# New_Multirotor_CPU_imu.net
KiCad netlist of a schematic drawn in EAGLE
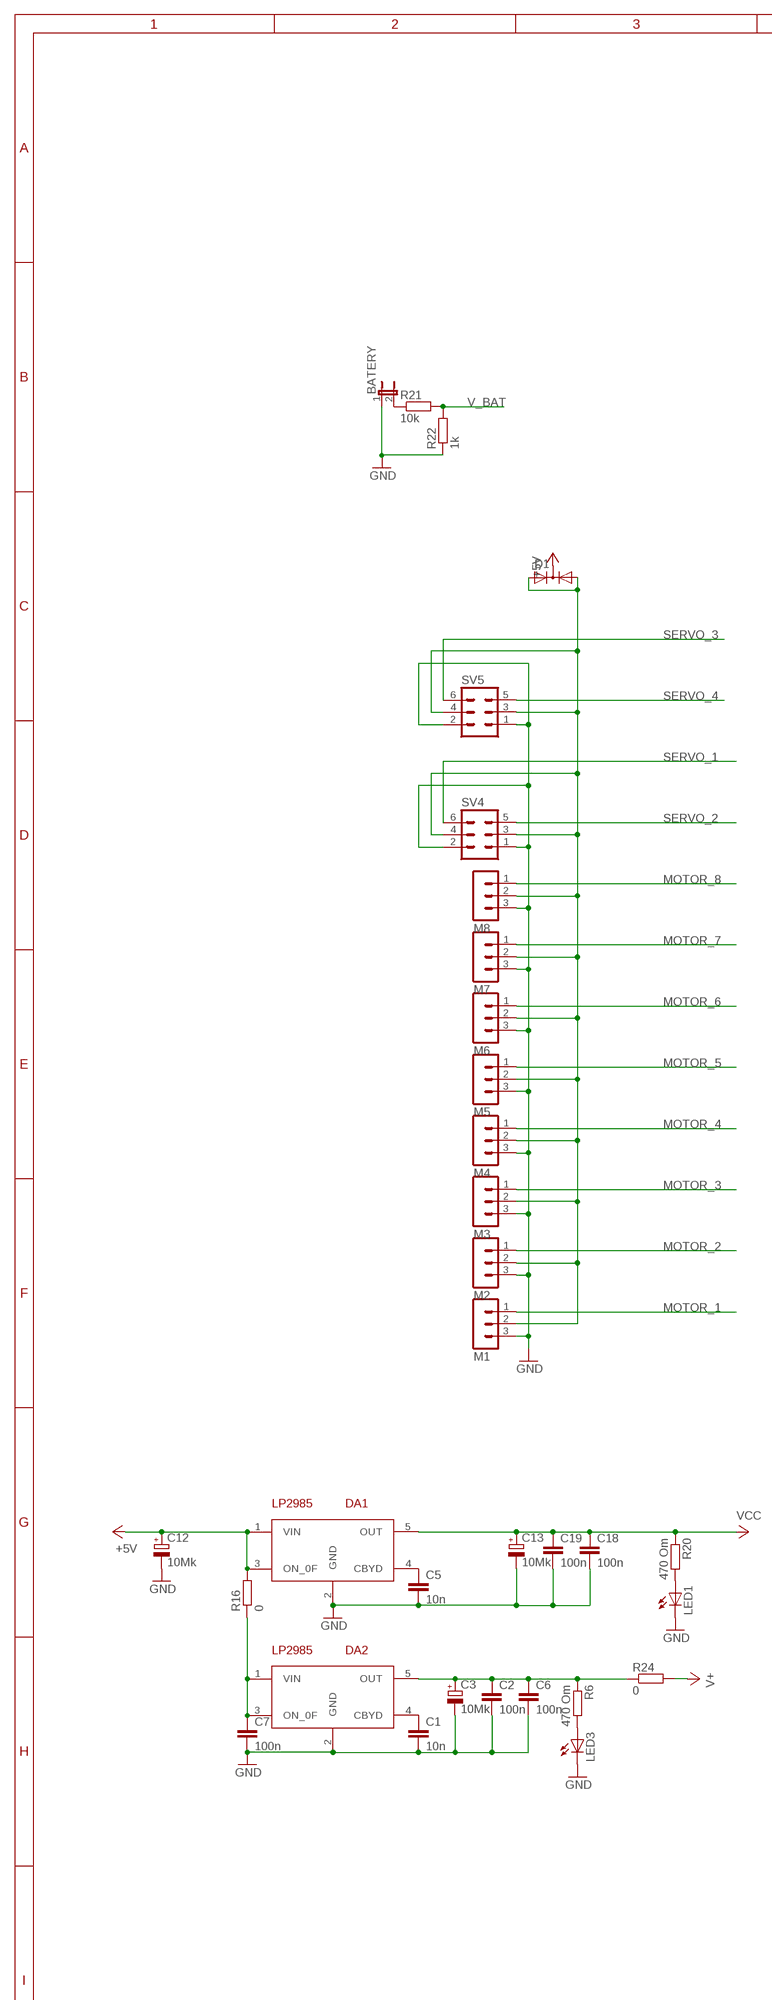
[diagram p0: schematic, sheet 1, part 1 of 2]
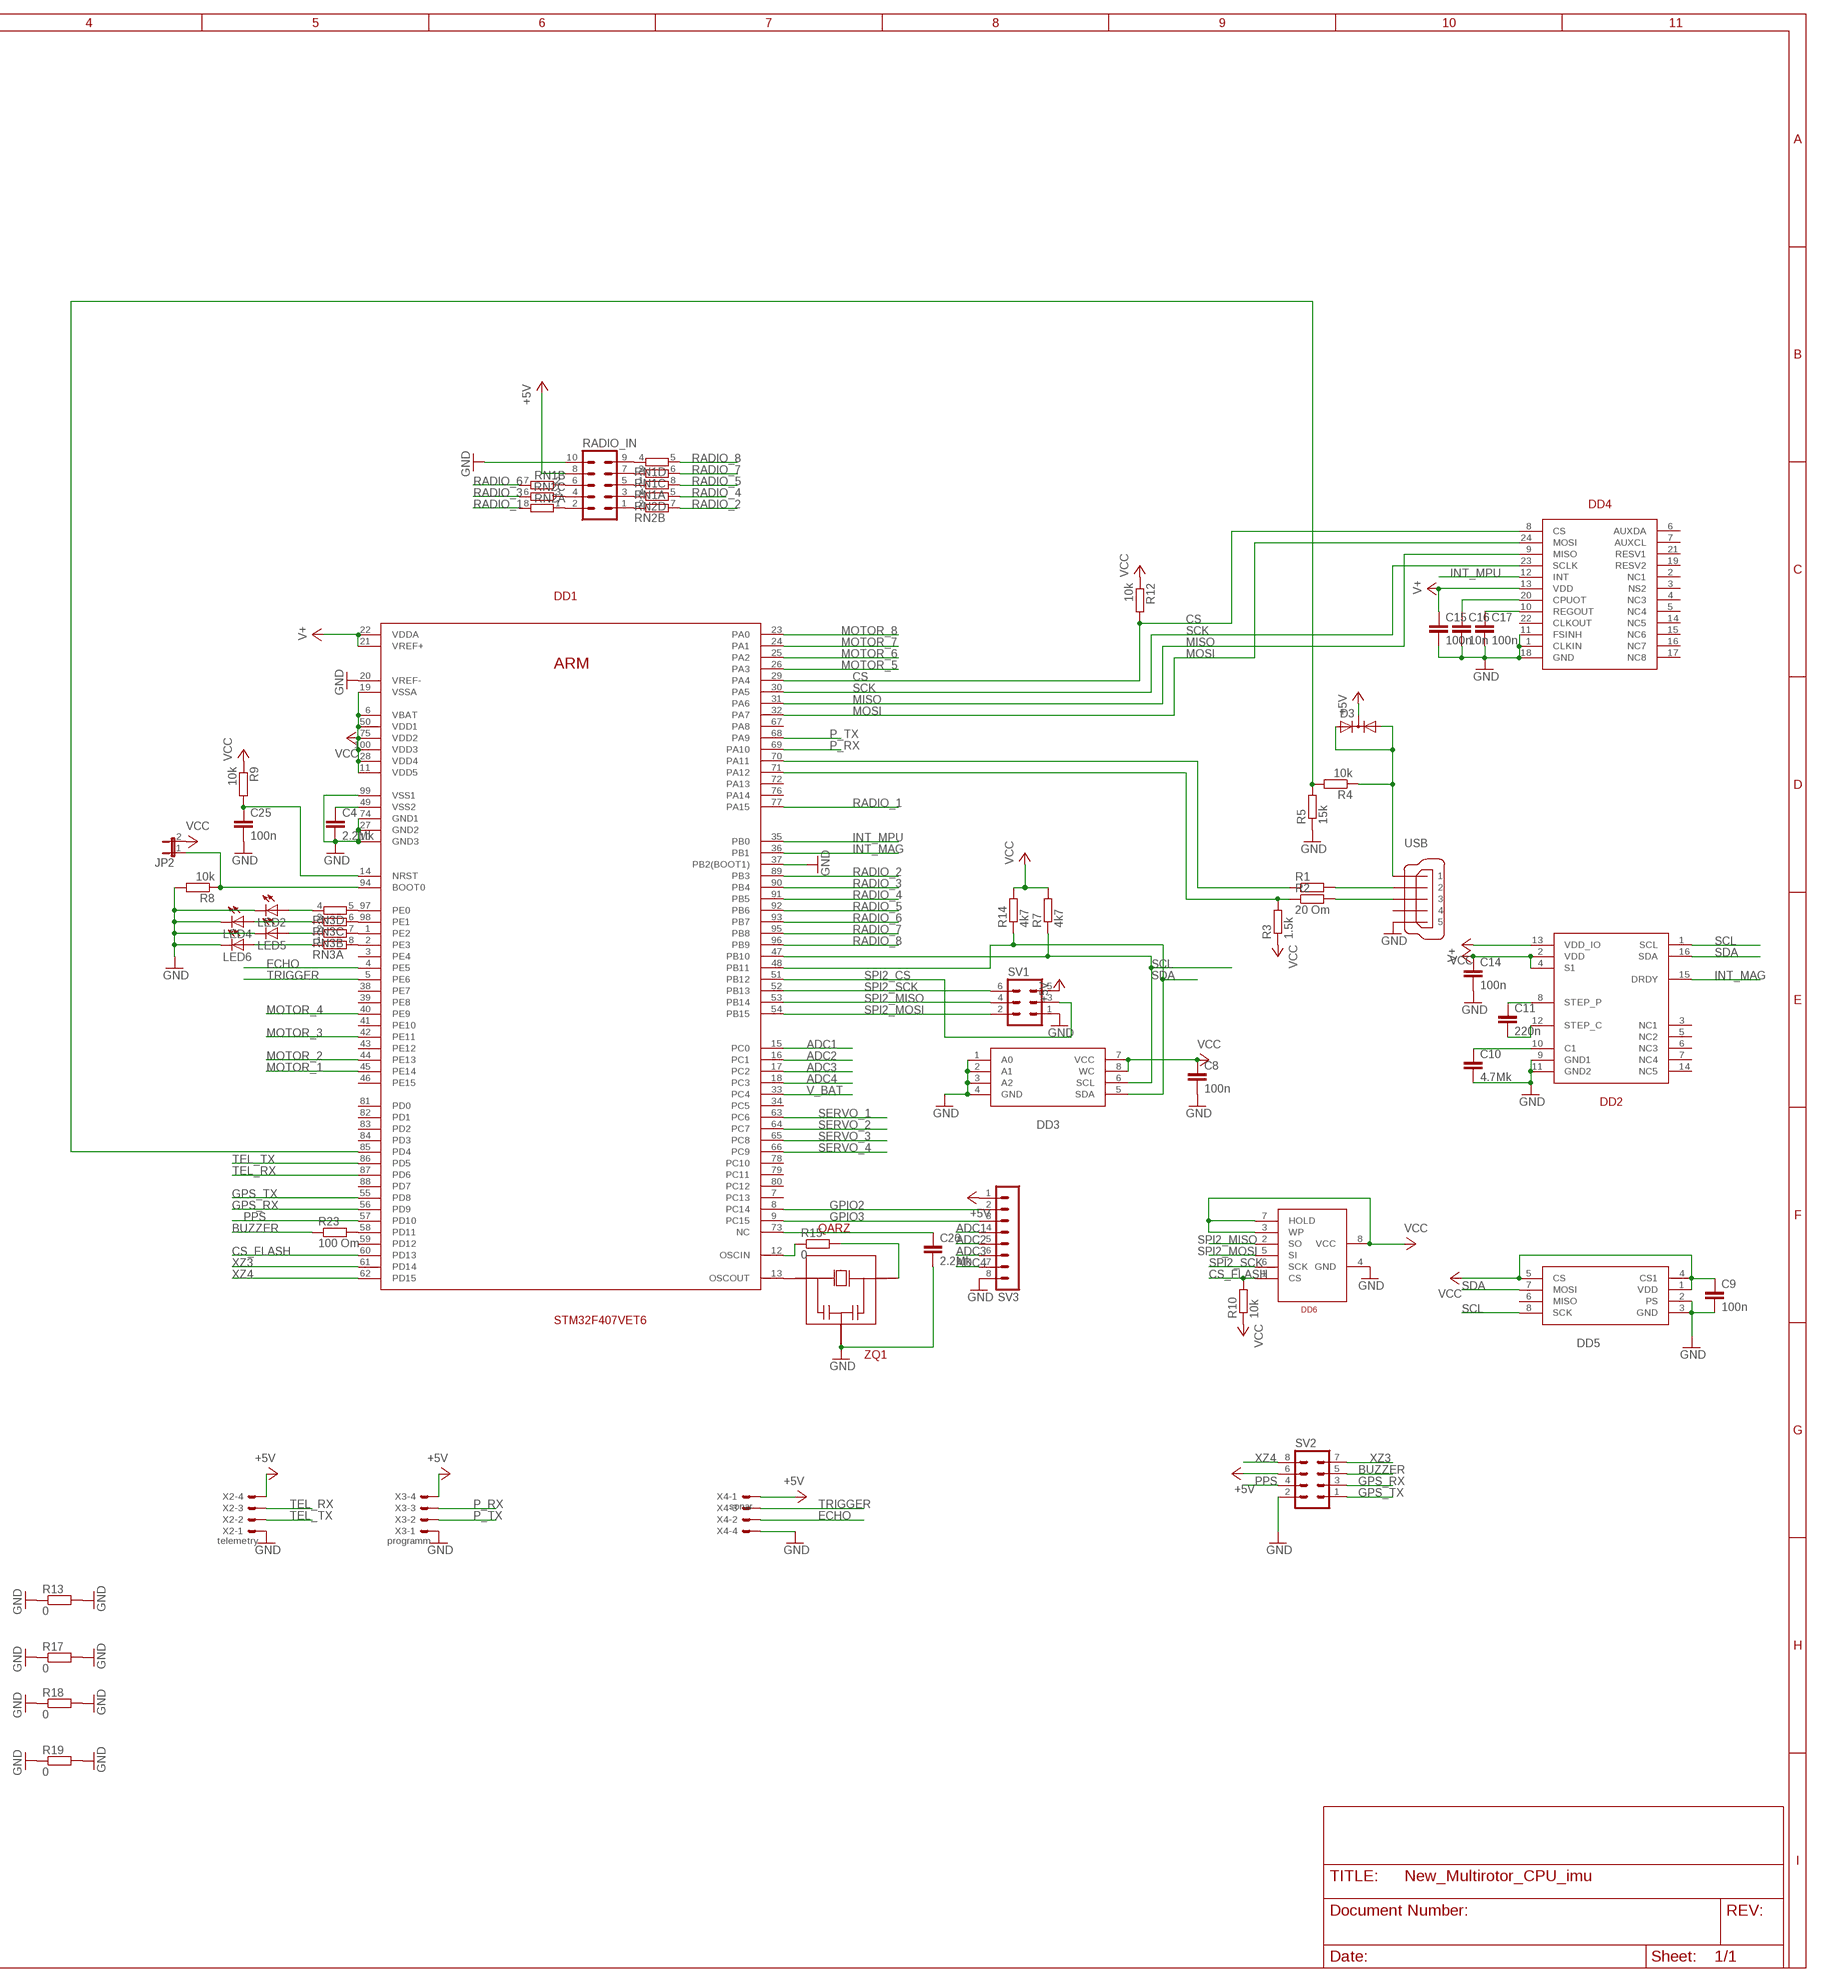
[diagram p1: schematic, sheet 1, part 2 of 2]

(export (version "E")
  (design (tool "Eeschema 10.0.6"))
  (components
    (comp (ref "BATERY")
      (value "JP1E")
      (footprint "eagle-import:JP1")
      (libsource (lib "eagle-import") (part "JP1E"))
    )
    (comp (ref "C1")
      (value "10n")
      (footprint "eagle-import:C0603K")
      (libsource (lib "eagle-import") (part "C-EUC0603K"))
    )
    (comp (ref "C2")
      (value "100n")
      (footprint "eagle-import:C0603K")
      (libsource (lib "eagle-import") (part "C-EUC0603K"))
    )
    (comp (ref "C3")
      (value "10Mk")
      (footprint "eagle-import:A_3216-18W")
      (libsource (lib "eagle-import") (part "CPOL-EUA/3216-18W"))
    )
    (comp (ref "C4")
      (value "2.2Mk")
      (footprint "eagle-import:C0603K")
      (libsource (lib "eagle-import") (part "C-EUC0603K"))
    )
    (comp (ref "C5")
      (value "10n")
      (footprint "eagle-import:C0603K")
      (libsource (lib "eagle-import") (part "C-EUC0603K"))
    )
    (comp (ref "C6")
      (value "100n")
      (footprint "eagle-import:C0603K")
      (libsource (lib "eagle-import") (part "C-EUC0603K"))
    )
    (comp (ref "C7")
      (value "100n")
      (footprint "eagle-import:C0603K")
      (libsource (lib "eagle-import") (part "C-EUC0603K"))
    )
    (comp (ref "C8")
      (value "100n")
      (footprint "eagle-import:C0603K")
      (libsource (lib "eagle-import") (part "C-EUC0603K"))
    )
    (comp (ref "C9")
      (value "100n")
      (footprint "eagle-import:C0603K")
      (libsource (lib "eagle-import") (part "C-EUC0603K"))
    )
    (comp (ref "C10")
      (value "4.7Mk")
      (footprint "eagle-import:C0603K")
      (libsource (lib "eagle-import") (part "C-EUC0603K"))
    )
    (comp (ref "C11")
      (value "220n")
      (footprint "eagle-import:C0603K")
      (libsource (lib "eagle-import") (part "C-EUC0603K"))
    )
    (comp (ref "C12")
      (value "10Mk")
      (footprint "eagle-import:A_3216-18W")
      (libsource (lib "eagle-import") (part "CPOL-EUA/3216-18W"))
    )
    (comp (ref "C13")
      (value "10Mk")
      (footprint "eagle-import:A_3216-18W")
      (libsource (lib "eagle-import") (part "CPOL-EUA/3216-18W"))
    )
    (comp (ref "C14")
      (value "100n")
      (footprint "eagle-import:C0603K")
      (libsource (lib "eagle-import") (part "C-EUC0603K"))
    )
    (comp (ref "C15")
      (value "100n")
      (footprint "eagle-import:C0603K")
      (libsource (lib "eagle-import") (part "C-EUC0603K"))
    )
    (comp (ref "C16")
      (value "10n")
      (footprint "eagle-import:C0603K")
      (libsource (lib "eagle-import") (part "C-EUC0603K"))
    )
    (comp (ref "C17")
      (value "100n")
      (footprint "eagle-import:C0603K")
      (libsource (lib "eagle-import") (part "C-EUC0603K"))
    )
    (comp (ref "C18")
      (value "100n")
      (footprint "eagle-import:C0603K")
      (libsource (lib "eagle-import") (part "C-EUC0603K"))
    )
    (comp (ref "C19")
      (value "100n")
      (footprint "eagle-import:C0603K")
      (libsource (lib "eagle-import") (part "C-EUC0603K"))
    )
    (comp (ref "C25")
      (value "100n")
      (footprint "eagle-import:C0603K")
      (libsource (lib "eagle-import") (part "C-EUC0603K"))
    )
    (comp (ref "C26")
      (value "2.2Mk")
      (footprint "eagle-import:C0603K")
      (libsource (lib "eagle-import") (part "C-EUC0603K"))
    )
    (comp (ref "D1")
      (value "DIODE-2AC|CASOT23")
      (footprint "eagle-import:SOT23")
      (libsource (lib "eagle-import") (part "DIODE-2AC|CASOT23"))
    )
    (comp (ref "D3")
      (value "DIODE-2AC|CASOT23")
      (footprint "eagle-import:SOT23")
      (libsource (lib "eagle-import") (part "DIODE-2AC|CASOT23"))
    )
    (comp (ref "DA1")
      (value "LP2985")
      (footprint "eagle-import:SOT23-5L")
      (libsource (lib "eagle-import") (part "3.3"))
    )
    (comp (ref "DA2")
      (value "LP2985")
      (footprint "eagle-import:SOT23-5L")
      (libsource (lib "eagle-import") (part "3.3"))
    )
    (comp (ref "DD1")
      (value "STM32F407VET6")
      (footprint "eagle-import:LQFP100")
      (libsource (lib "eagle-import") (part "STM32F407VET6"))
    )
    (comp (ref "DD2")
      (value "HMC5883L")
      (footprint "eagle-import:LCC-16")
      (libsource (lib "eagle-import") (part "HMC5883L"))
    )
    (comp (ref "DD3")
      (value "24C512")
      (footprint "eagle-import:SOIC8")
      (libsource (lib "eagle-import") (part "24C512"))
    )
    (comp (ref "DD4")
      (value "MPU6000")
      (footprint "eagle-import:JEDEC")
      (libsource (lib "eagle-import") (part "MPU6000"))
    )
    (comp (ref "DD5")
      (value "MS5611-01BA03")
      (footprint "eagle-import:MS5611-01BA03")
      (libsource (lib "eagle-import") (part "MS5611-01BA03"))
    )
    (comp (ref "DD6")
      (value "W25X40")
      (footprint "eagle-import:SOIC8")
      (libsource (lib "eagle-import") (part "W25X40"))
    )
    (comp (ref "JP2")
      (value "JP1E")
      (footprint "eagle-import:JP1")
      (libsource (lib "eagle-import") (part "JP1E"))
    )
    (comp (ref "LED1")
      (value "LEDCHIPLED_0603")
      (footprint "eagle-import:CHIPLED_0603")
      (libsource (lib "eagle-import") (part "LEDCHIPLED_0603"))
    )
    (comp (ref "LED2")
      (value "LEDCHIPLED_0603")
      (footprint "eagle-import:CHIPLED_0603")
      (libsource (lib "eagle-import") (part "LEDCHIPLED_0603"))
    )
    (comp (ref "LED3")
      (value "LEDCHIPLED_0603")
      (footprint "eagle-import:CHIPLED_0603")
      (libsource (lib "eagle-import") (part "LEDCHIPLED_0603"))
    )
    (comp (ref "LED4")
      (value "LEDCHIPLED_0603")
      (footprint "eagle-import:CHIPLED_0603")
      (libsource (lib "eagle-import") (part "LEDCHIPLED_0603"))
    )
    (comp (ref "LED5")
      (value "LEDCHIPLED_0603")
      (footprint "eagle-import:CHIPLED_0603")
      (libsource (lib "eagle-import") (part "LEDCHIPLED_0603"))
    )
    (comp (ref "LED6")
      (value "LEDCHIPLED_0603")
      (footprint "eagle-import:CHIPLED_0603")
      (libsource (lib "eagle-import") (part "LEDCHIPLED_0603"))
    )
    (comp (ref "M1")
      (value "MA03-1")
      (footprint "eagle-import:MA03-1")
      (fields (field (name "OC_FARNELL") "unknown") (field (name "OC_NEWARK") "unknown"))
      (libsource (lib "eagle-import") (part "MA03-1"))
    )
    (comp (ref "M2")
      (value "MA03-1")
      (footprint "eagle-import:MA03-1")
      (fields (field (name "OC_FARNELL") "unknown") (field (name "OC_NEWARK") "unknown"))
      (libsource (lib "eagle-import") (part "MA03-1"))
    )
    (comp (ref "M3")
      (value "MA03-1")
      (footprint "eagle-import:MA03-1")
      (fields (field (name "OC_FARNELL") "unknown") (field (name "OC_NEWARK") "unknown"))
      (libsource (lib "eagle-import") (part "MA03-1"))
    )
    (comp (ref "M4")
      (value "MA03-1")
      (footprint "eagle-import:MA03-1")
      (fields (field (name "OC_FARNELL") "unknown") (field (name "OC_NEWARK") "unknown"))
      (libsource (lib "eagle-import") (part "MA03-1"))
    )
    (comp (ref "M5")
      (value "MA03-1")
      (footprint "eagle-import:MA03-1")
      (fields (field (name "OC_FARNELL") "unknown") (field (name "OC_NEWARK") "unknown"))
      (libsource (lib "eagle-import") (part "MA03-1"))
    )
    (comp (ref "M6")
      (value "MA03-1")
      (footprint "eagle-import:MA03-1")
      (fields (field (name "OC_FARNELL") "unknown") (field (name "OC_NEWARK") "unknown"))
      (libsource (lib "eagle-import") (part "MA03-1"))
    )
    (comp (ref "M7")
      (value "MA03-1")
      (footprint "eagle-import:MA03-1")
      (fields (field (name "OC_FARNELL") "unknown") (field (name "OC_NEWARK") "unknown"))
      (libsource (lib "eagle-import") (part "MA03-1"))
    )
    (comp (ref "M8")
      (value "MA03-1")
      (footprint "eagle-import:MA03-1")
      (fields (field (name "OC_FARNELL") "unknown") (field (name "OC_NEWARK") "unknown"))
      (libsource (lib "eagle-import") (part "MA03-1"))
    )
    (comp (ref "R1")
      (value "R-EU_R0603")
      (footprint "eagle-import:R0603")
      (libsource (lib "eagle-import") (part "R-EU_R0603"))
    )
    (comp (ref "R2")
      (value "20 Om")
      (footprint "eagle-import:R0603")
      (libsource (lib "eagle-import") (part "R-EU_R0603"))
    )
    (comp (ref "R3")
      (value "1.5k")
      (footprint "eagle-import:R0603")
      (libsource (lib "eagle-import") (part "R-EU_R0603"))
    )
    (comp (ref "R4")
      (value "10k")
      (footprint "eagle-import:R0603")
      (libsource (lib "eagle-import") (part "R-EU_R0603"))
    )
    (comp (ref "R5")
      (value "15k")
      (footprint "eagle-import:R0603")
      (libsource (lib "eagle-import") (part "R-EU_R0603"))
    )
    (comp (ref "R6")
      (value "470 Om")
      (footprint "eagle-import:R0603")
      (libsource (lib "eagle-import") (part "R-EU_R0603"))
    )
    (comp (ref "R7")
      (value "4k7")
      (footprint "eagle-import:R0603")
      (libsource (lib "eagle-import") (part "R-EU_R0603"))
    )
    (comp (ref "R8")
      (value "10k")
      (footprint "eagle-import:R0603")
      (libsource (lib "eagle-import") (part "R-EU_R0603"))
    )
    (comp (ref "R9")
      (value "10k")
      (footprint "eagle-import:R0603")
      (libsource (lib "eagle-import") (part "R-EU_R0603"))
    )
    (comp (ref "R10")
      (value "10k")
      (footprint "eagle-import:R0603")
      (libsource (lib "eagle-import") (part "R-EU_R0603"))
    )
    (comp (ref "R12")
      (value "10k")
      (footprint "eagle-import:R0603")
      (libsource (lib "eagle-import") (part "R-EU_R0603"))
    )
    (comp (ref "R13")
      (value "0")
      (footprint "eagle-import:R0603")
      (libsource (lib "eagle-import") (part "R-EU_R0603"))
    )
    (comp (ref "R14")
      (value "4k7")
      (footprint "eagle-import:R0603")
      (libsource (lib "eagle-import") (part "R-EU_R0603"))
    )
    (comp (ref "R15")
      (value "0")
      (footprint "eagle-import:R0603")
      (libsource (lib "eagle-import") (part "R-EU_R0603"))
    )
    (comp (ref "R16")
      (value "0")
      (footprint "eagle-import:R0603")
      (libsource (lib "eagle-import") (part "R-EU_R0603"))
    )
    (comp (ref "R17")
      (value "0")
      (footprint "eagle-import:R0603")
      (libsource (lib "eagle-import") (part "R-EU_R0603"))
    )
    (comp (ref "R18")
      (value "0")
      (footprint "eagle-import:R0603")
      (libsource (lib "eagle-import") (part "R-EU_R0603"))
    )
    (comp (ref "R19")
      (value "0")
      (footprint "eagle-import:R0603")
      (libsource (lib "eagle-import") (part "R-EU_R0603"))
    )
    (comp (ref "R20")
      (value "470 Om")
      (footprint "eagle-import:R0603")
      (libsource (lib "eagle-import") (part "R-EU_R0603"))
    )
    (comp (ref "R21")
      (value "10k")
      (footprint "eagle-import:R0603")
      (libsource (lib "eagle-import") (part "R-EU_R0603"))
    )
    (comp (ref "R22")
      (value "1k")
      (footprint "eagle-import:R0603")
      (libsource (lib "eagle-import") (part "R-EU_R0603"))
    )
    (comp (ref "R23")
      (value "100 Om")
      (footprint "eagle-import:R0603")
      (libsource (lib "eagle-import") (part "R-EU_R0603"))
    )
    (comp (ref "R24")
      (value "0")
      (footprint "eagle-import:R0603")
      (libsource (lib "eagle-import") (part "R-EU_R0603"))
    )
    (comp (ref "RADIO_IN")
      (value "MA05-2")
      (footprint "eagle-import:MA05-2")
      (libsource (lib "eagle-import") (part "MA05-2"))
    )
    (comp (ref "RN1")
      (value "4R-N0603-ARV")
      (footprint "eagle-import:0603-ARV")
      (libsource (lib "eagle-import") (part "4R-N0603-ARV"))
    )
    (comp (ref "RN2")
      (value "4R-N0603-ARV")
      (footprint "eagle-import:0603-ARV")
      (libsource (lib "eagle-import") (part "4R-N0603-ARV"))
    )
    (comp (ref "RN3")
      (value "4R-N0603-ARV")
      (footprint "eagle-import:0603-ARV")
      (libsource (lib "eagle-import") (part "4R-N0603-ARV"))
    )
    (comp (ref "SV1")
      (value "MA03-2")
      (footprint "eagle-import:MA03-2")
      (libsource (lib "eagle-import") (part "MA03-2"))
    )
    (comp (ref "SV2")
      (value "MA04-2")
      (footprint "eagle-import:MA04-2")
      (libsource (lib "eagle-import") (part "MA04-2"))
    )
    (comp (ref "SV3")
      (value "MA08-1")
      (footprint "eagle-import:MA08-1")
      (libsource (lib "eagle-import") (part "MA08-1"))
    )
    (comp (ref "SV4")
      (value "MA03-2")
      (footprint "eagle-import:MA03-2")
      (libsource (lib "eagle-import") (part "MA03-2"))
    )
    (comp (ref "SV5")
      (value "MA03-2")
      (footprint "eagle-import:MA03-2")
      (libsource (lib "eagle-import") (part "MA03-2"))
    )
    (comp (ref "USB")
      (value "MINI-USB-32005-201")
      (footprint "eagle-import:32005-201")
      (libsource (lib "eagle-import") (part "MINI-USB-32005-201"))
    )
    (comp (ref "X2")
      (value "telemetry")
      (footprint "eagle-import:SM04B-SRSS-TB")
      (libsource (lib "eagle-import") (part "?M04B-SRSS-TBS"))
    )
    (comp (ref "X3")
      (value "programm")
      (footprint "eagle-import:SM04B-SRSS-TB")
      (libsource (lib "eagle-import") (part "?M04B-SRSS-TBS"))
    )
    (comp (ref "X4")
      (value "sonar")
      (footprint "eagle-import:SM04B-SRSS-TB")
      (libsource (lib "eagle-import") (part "?M04B-SRSS-TBS"))
    )
    (comp (ref "ZQ1")
      (value "QARZ")
      (footprint "eagle-import:QARZ")
      (libsource (lib "eagle-import") (part "QARZ"))
    )
  )
  (nets
    (net (code "1") (name "+5V") (class "Default")
      (node (ref "C12") (pin "+") (pinfunction "+_+") (pintype "passive"))
      (node (ref "D1") (pin "3") (pinfunction "C_3") (pintype "passive"))
      (node (ref "D3") (pin "3") (pinfunction "C_3") (pintype "passive"))
      (node (ref "DA1") (pin "1") (pinfunction "VIN_1") (pintype "bidirectional"))
      (node (ref "DA1") (pin "3") (pinfunction "ON_0F_3") (pintype "bidirectional"))
      (node (ref "R16") (pin "2") (pinfunction "2_2") (pintype "passive"))
      (node (ref "RADIO_IN") (pin "8") (pinfunction "8_8") (pintype "passive"))
      (node (ref "SV1") (pin "5") (pinfunction "5_5") (pintype "passive"))
      (node (ref "SV2") (pin "6") (pinfunction "6_6") (pintype "passive"))
      (node (ref "SV3") (pin "1") (pinfunction "1_1") (pintype "passive"))
      (node (ref "X2") (pin "4") (pinfunction "S_4") (pintype "passive"))
      (node (ref "X3") (pin "4") (pinfunction "S_4") (pintype "passive"))
      (node (ref "X4") (pin "1") (pinfunction "S_1") (pintype "passive"))
    )
    (net (code "2") (name "/ADC1") (class "Default")
      (node (ref "DD1") (pin "15") (pinfunction "PC0_15") (pintype "bidirectional"))
      (node (ref "SV3") (pin "4") (pinfunction "4_4") (pintype "passive"))
    )
    (net (code "3") (name "/ADC2") (class "Default")
      (node (ref "DD1") (pin "16") (pinfunction "PC1_16") (pintype "bidirectional"))
      (node (ref "SV3") (pin "5") (pinfunction "5_5") (pintype "passive"))
    )
    (net (code "4") (name "/ADC3") (class "Default")
      (node (ref "DD1") (pin "17") (pinfunction "PC2_17") (pintype "bidirectional"))
      (node (ref "SV3") (pin "6") (pinfunction "6_6") (pintype "passive"))
    )
    (net (code "5") (name "/ADC4") (class "Default")
      (node (ref "DD1") (pin "18") (pinfunction "PC3_18") (pintype "bidirectional"))
      (node (ref "SV3") (pin "7") (pinfunction "7_7") (pintype "passive"))
    )
    (net (code "6") (name "/BUZZER") (class "Default")
      (node (ref "R23") (pin "1") (pinfunction "1_1") (pintype "passive"))
      (node (ref "SV2") (pin "5") (pinfunction "5_5") (pintype "passive"))
    )
    (net (code "7") (name "/CS") (class "Default")
      (node (ref "DD1") (pin "29") (pinfunction "PA4_29") (pintype "bidirectional"))
      (node (ref "DD4") (pin "8") (pinfunction "CS_8") (pintype "bidirectional"))
      (node (ref "R12") (pin "2") (pinfunction "2_2") (pintype "passive"))
    )
    (net (code "8") (name "/CS_FLASH") (class "Default")
      (node (ref "DD1") (pin "60") (pinfunction "PD13_60") (pintype "bidirectional"))
      (node (ref "DD6") (pin "1") (pinfunction "CS_1") (pintype "bidirectional"))
      (node (ref "R10") (pin "2") (pinfunction "2_2") (pintype "passive"))
    )
    (net (code "9") (name "/ECHO") (class "Default")
      (node (ref "DD1") (pin "4") (pinfunction "PE5_4") (pintype "bidirectional"))
      (node (ref "X4") (pin "2") (pinfunction "S_2") (pintype "passive"))
    )
    (net (code "10") (name "/GPIO2") (class "Default")
      (node (ref "DD1") (pin "8") (pinfunction "PC14_8") (pintype "bidirectional"))
      (node (ref "SV3") (pin "2") (pinfunction "2_2") (pintype "passive"))
    )
    (net (code "11") (name "/GPIO3") (class "Default")
      (node (ref "DD1") (pin "9") (pinfunction "PC15_9") (pintype "bidirectional"))
      (node (ref "SV3") (pin "3") (pinfunction "3_3") (pintype "passive"))
    )
    (net (code "12") (name "/GPS_RX") (class "Default")
      (node (ref "DD1") (pin "56") (pinfunction "PD9_56") (pintype "bidirectional"))
      (node (ref "SV2") (pin "3") (pinfunction "3_3") (pintype "passive"))
    )
    (net (code "13") (name "/GPS_TX") (class "Default")
      (node (ref "DD1") (pin "55") (pinfunction "PD8_55") (pintype "bidirectional"))
      (node (ref "SV2") (pin "1") (pinfunction "1_1") (pintype "passive"))
    )
    (net (code "14") (name "/INT_MAG") (class "Default")
      (node (ref "DD1") (pin "36") (pinfunction "PB1_36") (pintype "bidirectional"))
      (node (ref "DD2") (pin "15") (pinfunction "DRDY_15") (pintype "bidirectional"))
    )
    (net (code "15") (name "/INT_MPU") (class "Default")
      (node (ref "DD1") (pin "35") (pinfunction "PB0_35") (pintype "bidirectional"))
      (node (ref "DD4") (pin "12") (pinfunction "INT_12") (pintype "bidirectional"))
    )
    (net (code "16") (name "/MISO") (class "Default")
      (node (ref "DD1") (pin "31") (pinfunction "PA6_31") (pintype "bidirectional"))
      (node (ref "DD4") (pin "9") (pinfunction "MISO_9") (pintype "bidirectional"))
    )
    (net (code "17") (name "/MOSI") (class "Default")
      (node (ref "DD1") (pin "32") (pinfunction "PA7_32") (pintype "bidirectional"))
      (node (ref "DD4") (pin "24") (pinfunction "MOSI_24") (pintype "bidirectional"))
    )
    (net (code "18") (name "/MOTOR_1") (class "Default")
      (node (ref "DD1") (pin "45") (pinfunction "PE14_45") (pintype "bidirectional"))
      (node (ref "M1") (pin "1") (pinfunction "1_1") (pintype "passive"))
    )
    (net (code "19") (name "/MOTOR_2") (class "Default")
      (node (ref "DD1") (pin "44") (pinfunction "PE13_44") (pintype "bidirectional"))
      (node (ref "M2") (pin "1") (pinfunction "1_1") (pintype "passive"))
    )
    (net (code "20") (name "/MOTOR_3") (class "Default")
      (node (ref "DD1") (pin "42") (pinfunction "PE11_42") (pintype "bidirectional"))
      (node (ref "M3") (pin "1") (pinfunction "1_1") (pintype "passive"))
    )
    (net (code "21") (name "/MOTOR_4") (class "Default")
      (node (ref "DD1") (pin "40") (pinfunction "PE9_40") (pintype "bidirectional"))
      (node (ref "M4") (pin "1") (pinfunction "1_1") (pintype "passive"))
    )
    (net (code "22") (name "/MOTOR_5") (class "Default")
      (node (ref "DD1") (pin "26") (pinfunction "PA3_26") (pintype "bidirectional"))
      (node (ref "M5") (pin "1") (pinfunction "1_1") (pintype "passive"))
    )
    (net (code "23") (name "/MOTOR_6") (class "Default")
      (node (ref "DD1") (pin "25") (pinfunction "PA2_25") (pintype "bidirectional"))
      (node (ref "M6") (pin "1") (pinfunction "1_1") (pintype "passive"))
    )
    (net (code "24") (name "/MOTOR_7") (class "Default")
      (node (ref "DD1") (pin "24") (pinfunction "PA1_24") (pintype "bidirectional"))
      (node (ref "M7") (pin "1") (pinfunction "1_1") (pintype "passive"))
    )
    (net (code "25") (name "/MOTOR_8") (class "Default")
      (node (ref "DD1") (pin "23") (pinfunction "PA0_23") (pintype "bidirectional"))
      (node (ref "M8") (pin "1") (pinfunction "1_1") (pintype "passive"))
    )
    (net (code "26") (name "/PPS") (class "Default")
      (node (ref "DD1") (pin "57") (pinfunction "PD10_57") (pintype "bidirectional"))
      (node (ref "SV2") (pin "4") (pinfunction "4_4") (pintype "passive"))
    )
    (net (code "27") (name "/P_RX") (class "Default")
      (node (ref "DD1") (pin "69") (pinfunction "PA10_69") (pintype "bidirectional"))
      (node (ref "X3") (pin "3") (pinfunction "S_3") (pintype "passive"))
    )
    (net (code "28") (name "/P_TX") (class "Default")
      (node (ref "DD1") (pin "68") (pinfunction "PA9_68") (pintype "bidirectional"))
      (node (ref "X3") (pin "2") (pinfunction "S_2") (pintype "passive"))
    )
    (net (code "29") (name "/RADIO_1") (class "Default")
      (node (ref "DD1") (pin "77") (pinfunction "PA15_77") (pintype "bidirectional"))
      (node (ref "RN2") (pin "8") (pinfunction "2_8") (pintype "passive"))
    )
    (net (code "30") (name "/RADIO_2") (class "Default")
      (node (ref "DD1") (pin "89") (pinfunction "PB3_89") (pintype "bidirectional"))
      (node (ref "RN2") (pin "7") (pinfunction "2_7") (pintype "passive"))
    )
    (net (code "31") (name "/RADIO_3") (class "Default")
      (node (ref "DD1") (pin "90") (pinfunction "PB4_90") (pintype "bidirectional"))
      (node (ref "RN2") (pin "6") (pinfunction "2_6") (pintype "passive"))
    )
    (net (code "32") (name "/RADIO_4") (class "Default")
      (node (ref "DD1") (pin "91") (pinfunction "PB5_91") (pintype "bidirectional"))
      (node (ref "RN2") (pin "5") (pinfunction "2_5") (pintype "passive"))
    )
    (net (code "33") (name "/RADIO_5") (class "Default")
      (node (ref "DD1") (pin "92") (pinfunction "PB6_92") (pintype "bidirectional"))
      (node (ref "RN1") (pin "8") (pinfunction "2_8") (pintype "passive"))
    )
    (net (code "34") (name "/RADIO_6") (class "Default")
      (node (ref "DD1") (pin "93") (pinfunction "PB7_93") (pintype "bidirectional"))
      (node (ref "RN1") (pin "7") (pinfunction "2_7") (pintype "passive"))
    )
    (net (code "35") (name "/RADIO_7") (class "Default")
      (node (ref "DD1") (pin "95") (pinfunction "PB8_95") (pintype "bidirectional"))
      (node (ref "RN1") (pin "6") (pinfunction "2_6") (pintype "passive"))
    )
    (net (code "36") (name "/RADIO_8") (class "Default")
      (node (ref "DD1") (pin "96") (pinfunction "PB9_96") (pintype "bidirectional"))
      (node (ref "RN1") (pin "5") (pinfunction "2_5") (pintype "passive"))
    )
    (net (code "37") (name "/SCK") (class "Default")
      (node (ref "DD1") (pin "30") (pinfunction "PA5_30") (pintype "bidirectional"))
      (node (ref "DD4") (pin "23") (pinfunction "SCLK_23") (pintype "bidirectional"))
    )
    (net (code "38") (name "/SCL") (class "Default")
      (node (ref "DD1") (pin "47") (pinfunction "PB10_47") (pintype "bidirectional"))
      (node (ref "DD2") (pin "1") (pinfunction "SCL_1") (pintype "bidirectional"))
      (node (ref "DD3") (pin "6") (pinfunction "SCL_6") (pintype "bidirectional"))
      (node (ref "DD5") (pin "8") (pinfunction "SCK_8") (pintype "bidirectional"))
      (node (ref "R7") (pin "1") (pinfunction "1_1") (pintype "passive"))
    )
    (net (code "39") (name "/SDA") (class "Default")
      (node (ref "DD1") (pin "48") (pinfunction "PB11_48") (pintype "bidirectional"))
      (node (ref "DD2") (pin "16") (pinfunction "SDA_16") (pintype "bidirectional"))
      (node (ref "DD3") (pin "5") (pinfunction "SDA_5") (pintype "bidirectional"))
      (node (ref "DD5") (pin "7") (pinfunction "MOSI_7") (pintype "bidirectional"))
      (node (ref "R14") (pin "1") (pinfunction "1_1") (pintype "passive"))
    )
    (net (code "40") (name "/SERVO_1") (class "Default")
      (node (ref "DD1") (pin "63") (pinfunction "PC6_63") (pintype "bidirectional"))
      (node (ref "SV4") (pin "6") (pinfunction "6_6") (pintype "passive"))
    )
    (net (code "41") (name "/SERVO_2") (class "Default")
      (node (ref "DD1") (pin "64") (pinfunction "PC7_64") (pintype "bidirectional"))
      (node (ref "SV4") (pin "5") (pinfunction "5_5") (pintype "passive"))
    )
    (net (code "42") (name "/SERVO_3") (class "Default")
      (node (ref "DD1") (pin "65") (pinfunction "PC8_65") (pintype "bidirectional"))
      (node (ref "SV5") (pin "6") (pinfunction "6_6") (pintype "passive"))
    )
    (net (code "43") (name "/SERVO_4") (class "Default")
      (node (ref "DD1") (pin "66") (pinfunction "PC9_66") (pintype "bidirectional"))
      (node (ref "SV5") (pin "5") (pinfunction "5_5") (pintype "passive"))
    )
    (net (code "44") (name "/SPI2_CS") (class "Default")
      (node (ref "DD1") (pin "51") (pinfunction "PB12_51") (pintype "bidirectional"))
      (node (ref "SV1") (pin "3") (pinfunction "3_3") (pintype "passive"))
    )
    (net (code "45") (name "/SPI2_MISO") (class "Default")
      (node (ref "DD1") (pin "53") (pinfunction "PB14_53") (pintype "bidirectional"))
      (node (ref "DD6") (pin "2") (pinfunction "SO_2") (pintype "bidirectional"))
      (node (ref "SV1") (pin "4") (pinfunction "4_4") (pintype "passive"))
    )
    (net (code "46") (name "/SPI2_MOSI") (class "Default")
      (node (ref "DD1") (pin "54") (pinfunction "PB15_54") (pintype "bidirectional"))
      (node (ref "DD6") (pin "5") (pinfunction "SI_5") (pintype "bidirectional"))
      (node (ref "SV1") (pin "2") (pinfunction "2_2") (pintype "passive"))
    )
    (net (code "47") (name "/SPI2_SCK") (class "Default")
      (node (ref "DD1") (pin "52") (pinfunction "PB13_52") (pintype "bidirectional"))
      (node (ref "DD6") (pin "6") (pinfunction "SCK_6") (pintype "bidirectional"))
      (node (ref "SV1") (pin "6") (pinfunction "6_6") (pintype "passive"))
    )
    (net (code "48") (name "/TEL_RX") (class "Default")
      (node (ref "DD1") (pin "87") (pinfunction "PD6_87") (pintype "bidirectional"))
      (node (ref "X2") (pin "3") (pinfunction "S_3") (pintype "passive"))
    )
    (net (code "49") (name "/TEL_TX") (class "Default")
      (node (ref "DD1") (pin "86") (pinfunction "PD5_86") (pintype "bidirectional"))
      (node (ref "X2") (pin "2") (pinfunction "S_2") (pintype "passive"))
    )
    (net (code "50") (name "/TRIGGER") (class "Default")
      (node (ref "DD1") (pin "5") (pinfunction "PE6_5") (pintype "bidirectional"))
      (node (ref "X4") (pin "3") (pinfunction "S_3") (pintype "passive"))
    )
    (net (code "51") (name "/V_BAT") (class "Default")
      (node (ref "DD1") (pin "33") (pinfunction "PC4_33") (pintype "bidirectional"))
      (node (ref "R21") (pin "2") (pinfunction "2_2") (pintype "passive"))
      (node (ref "R22") (pin "2") (pinfunction "2_2") (pintype "passive"))
    )
    (net (code "52") (name "/XZ3") (class "Default")
      (node (ref "DD1") (pin "61") (pinfunction "PD14_61") (pintype "bidirectional"))
      (node (ref "SV2") (pin "7") (pinfunction "7_7") (pintype "passive"))
    )
    (net (code "53") (name "/XZ4") (class "Default")
      (node (ref "DD1") (pin "62") (pinfunction "PD15_62") (pintype "bidirectional"))
      (node (ref "SV2") (pin "8") (pinfunction "8_8") (pintype "passive"))
    )
    (net (code "54") (name "GND") (class "Default")
      (node (ref "BATERY") (pin "1") (pinfunction "1_1") (pintype "passive"))
      (node (ref "C1") (pin "2") (pinfunction "2_2") (pintype "passive"))
      (node (ref "C10") (pin "2") (pinfunction "2_2") (pintype "passive"))
      (node (ref "C12") (pin "-") (pinfunction "-_-") (pintype "passive"))
      (node (ref "C13") (pin "-") (pinfunction "-_-") (pintype "passive"))
      (node (ref "C14") (pin "2") (pinfunction "2_2") (pintype "passive"))
      (node (ref "C15") (pin "2") (pinfunction "2_2") (pintype "passive"))
      (node (ref "C16") (pin "2") (pinfunction "2_2") (pintype "passive"))
      (node (ref "C17") (pin "2") (pinfunction "2_2") (pintype "passive"))
      (node (ref "C18") (pin "2") (pinfunction "2_2") (pintype "passive"))
      (node (ref "C19") (pin "2") (pinfunction "2_2") (pintype "passive"))
      (node (ref "C2") (pin "2") (pinfunction "2_2") (pintype "passive"))
      (node (ref "C25") (pin "2") (pinfunction "2_2") (pintype "passive"))
      (node (ref "C26") (pin "2") (pinfunction "2_2") (pintype "passive"))
      (node (ref "C3") (pin "-") (pinfunction "-_-") (pintype "passive"))
      (node (ref "C4") (pin "2") (pinfunction "2_2") (pintype "passive"))
      (node (ref "C5") (pin "2") (pinfunction "2_2") (pintype "passive"))
      (node (ref "C6") (pin "2") (pinfunction "2_2") (pintype "passive"))
      (node (ref "C7") (pin "2") (pinfunction "2_2") (pintype "passive"))
      (node (ref "C8") (pin "2") (pinfunction "2_2") (pintype "passive"))
      (node (ref "C9") (pin "2") (pinfunction "2_2") (pintype "passive"))
      (node (ref "DA1") (pin "2") (pinfunction "GND_2") (pintype "bidirectional"))
      (node (ref "DA2") (pin "2") (pinfunction "GND_2") (pintype "bidirectional"))
      (node (ref "DD1") (pin "10") (pinfunction "GND3_10") (pintype "bidirectional"))
      (node (ref "DD1") (pin "20") (pinfunction "VREF-_20") (pintype "bidirectional"))
      (node (ref "DD1") (pin "27") (pinfunction "GND2_27") (pintype "bidirectional"))
      (node (ref "DD1") (pin "37") (pinfunction "PB2(BOOT1)_37") (pintype "bidirectional"))
      (node (ref "DD1") (pin "74") (pinfunction "GND1_74") (pintype "bidirectional"))
      (node (ref "DD1") (pin "99") (pinfunction "VSS1_99") (pintype "bidirectional"))
      (node (ref "DD2") (pin "11") (pinfunction "GND2_11") (pintype "bidirectional"))
      (node (ref "DD2") (pin "9") (pinfunction "GND1_9") (pintype "bidirectional"))
      (node (ref "DD3") (pin "1") (pinfunction "A0_1") (pintype "bidirectional"))
      (node (ref "DD3") (pin "2") (pinfunction "A1_2") (pintype "bidirectional"))
      (node (ref "DD3") (pin "3") (pinfunction "A2_3") (pintype "bidirectional"))
      (node (ref "DD3") (pin "4") (pinfunction "GND_4") (pintype "bidirectional"))
      (node (ref "DD4") (pin "1") (pinfunction "CLKIN_1") (pintype "bidirectional"))
      (node (ref "DD4") (pin "11") (pinfunction "FSINH_11") (pintype "bidirectional"))
      (node (ref "DD4") (pin "18") (pinfunction "GND_18") (pintype "bidirectional"))
      (node (ref "DD5") (pin "2") (pinfunction "PS_2") (pintype "bidirectional"))
      (node (ref "DD5") (pin "3") (pinfunction "GND_3") (pintype "bidirectional"))
      (node (ref "DD6") (pin "4") (pinfunction "GND_4") (pintype "bidirectional"))
      (node (ref "LED1") (pin "C") (pinfunction "C_C") (pintype "passive"))
      (node (ref "LED2") (pin "C") (pinfunction "C_C") (pintype "passive"))
      (node (ref "LED3") (pin "C") (pinfunction "C_C") (pintype "passive"))
      (node (ref "LED4") (pin "C") (pinfunction "C_C") (pintype "passive"))
      (node (ref "LED5") (pin "C") (pinfunction "C_C") (pintype "passive"))
      (node (ref "LED6") (pin "C") (pinfunction "C_C") (pintype "passive"))
      (node (ref "M1") (pin "3") (pinfunction "3_3") (pintype "passive"))
      (node (ref "M2") (pin "3") (pinfunction "3_3") (pintype "passive"))
      (node (ref "M3") (pin "3") (pinfunction "3_3") (pintype "passive"))
      (node (ref "M4") (pin "3") (pinfunction "3_3") (pintype "passive"))
      (node (ref "M5") (pin "3") (pinfunction "3_3") (pintype "passive"))
      (node (ref "M6") (pin "3") (pinfunction "3_3") (pintype "passive"))
      (node (ref "M7") (pin "3") (pinfunction "3_3") (pintype "passive"))
      (node (ref "M8") (pin "3") (pinfunction "3_3") (pintype "passive"))
      (node (ref "R13") (pin "1") (pinfunction "1_1") (pintype "passive"))
      (node (ref "R13") (pin "2") (pinfunction "2_2") (pintype "passive"))
      (node (ref "R17") (pin "1") (pinfunction "1_1") (pintype "passive"))
      (node (ref "R17") (pin "2") (pinfunction "2_2") (pintype "passive"))
      (node (ref "R18") (pin "1") (pinfunction "1_1") (pintype "passive"))
      (node (ref "R18") (pin "2") (pinfunction "2_2") (pintype "passive"))
      (node (ref "R19") (pin "1") (pinfunction "1_1") (pintype "passive"))
      (node (ref "R19") (pin "2") (pinfunction "2_2") (pintype "passive"))
      (node (ref "R22") (pin "1") (pinfunction "1_1") (pintype "passive"))
      (node (ref "R5") (pin "1") (pinfunction "1_1") (pintype "passive"))
      (node (ref "R8") (pin "2") (pinfunction "2_2") (pintype "passive"))
      (node (ref "RADIO_IN") (pin "10") (pinfunction "10_10") (pintype "passive"))
      (node (ref "SV1") (pin "1") (pinfunction "1_1") (pintype "passive"))
      (node (ref "SV2") (pin "2") (pinfunction "2_2") (pintype "passive"))
      (node (ref "SV3") (pin "8") (pinfunction "8_8") (pintype "passive"))
      (node (ref "SV4") (pin "1") (pinfunction "1_1") (pintype "passive"))
      (node (ref "SV4") (pin "2") (pinfunction "2_2") (pintype "passive"))
      (node (ref "SV5") (pin "1") (pinfunction "1_1") (pintype "passive"))
      (node (ref "SV5") (pin "2") (pinfunction "2_2") (pintype "passive"))
      (node (ref "USB") (pin "5") (pinfunction "5_5") (pintype "passive"))
      (node (ref "X2") (pin "1") (pinfunction "S_1") (pintype "passive"))
      (node (ref "X3") (pin "1") (pinfunction "S_1") (pintype "passive"))
      (node (ref "X4") (pin "4") (pinfunction "S_4") (pintype "passive"))
      (node (ref "ZQ1") (pin "2") (pinfunction "2_2") (pintype "bidirectional"))
    )
    (net (code "55") (name "Net-(BATERY-Pad2)") (class "Default")
      (node (ref "BATERY") (pin "2") (pinfunction "2_2") (pintype "passive"))
      (node (ref "R21") (pin "1") (pinfunction "1_1") (pintype "passive"))
    )
    (net (code "56") (name "Net-(D1-A1)") (class "Default")
      (node (ref "D1") (pin "1") (pinfunction "A1_1") (pintype "passive"))
      (node (ref "D1") (pin "2") (pinfunction "A2_2") (pintype "passive"))
      (node (ref "M1") (pin "2") (pinfunction "2_2") (pintype "passive"))
      (node (ref "M2") (pin "2") (pinfunction "2_2") (pintype "passive"))
      (node (ref "M3") (pin "2") (pinfunction "2_2") (pintype "passive"))
      (node (ref "M4") (pin "2") (pinfunction "2_2") (pintype "passive"))
      (node (ref "M5") (pin "2") (pinfunction "2_2") (pintype "passive"))
      (node (ref "M6") (pin "2") (pinfunction "2_2") (pintype "passive"))
      (node (ref "M7") (pin "2") (pinfunction "2_2") (pintype "passive"))
      (node (ref "M8") (pin "2") (pinfunction "2_2") (pintype "passive"))
      (node (ref "SV4") (pin "3") (pinfunction "3_3") (pintype "passive"))
      (node (ref "SV4") (pin "4") (pinfunction "4_4") (pintype "passive"))
      (node (ref "SV5") (pin "3") (pinfunction "3_3") (pintype "passive"))
      (node (ref "SV5") (pin "4") (pinfunction "4_4") (pintype "passive"))
    )
    (net (code "57") (name "Net-(D3-A1)") (class "Default")
      (node (ref "D3") (pin "1") (pinfunction "A1_1") (pintype "passive"))
      (node (ref "D3") (pin "2") (pinfunction "A2_2") (pintype "passive"))
      (node (ref "R4") (pin "1") (pinfunction "1_1") (pintype "passive"))
      (node (ref "USB") (pin "1") (pinfunction "1_1") (pintype "passive"))
    )
    (net (code "58") (name "Net-(DA1-CBYD)") (class "Default")
      (node (ref "C5") (pin "1") (pinfunction "1_1") (pintype "passive"))
      (node (ref "DA1") (pin "4") (pinfunction "CBYD_4") (pintype "bidirectional"))
    )
    (net (code "59") (name "Net-(DA2-CBYD)") (class "Default")
      (node (ref "C1") (pin "1") (pinfunction "1_1") (pintype "passive"))
      (node (ref "DA2") (pin "4") (pinfunction "CBYD_4") (pintype "bidirectional"))
    )
    (net (code "60") (name "Net-(DA2-ON_0F)") (class "Default")
      (node (ref "C7") (pin "1") (pinfunction "1_1") (pintype "passive"))
      (node (ref "DA2") (pin "1") (pinfunction "VIN_1") (pintype "bidirectional"))
      (node (ref "DA2") (pin "3") (pinfunction "ON_0F_3") (pintype "bidirectional"))
      (node (ref "R16") (pin "1") (pinfunction "1_1") (pintype "passive"))
    )
    (net (code "61") (name "Net-(DA2-OUT)") (class "Default")
      (node (ref "C2") (pin "1") (pinfunction "1_1") (pintype "passive"))
      (node (ref "C3") (pin "+") (pinfunction "+_+") (pintype "passive"))
      (node (ref "C6") (pin "1") (pinfunction "1_1") (pintype "passive"))
      (node (ref "DA2") (pin "5") (pinfunction "OUT_5") (pintype "bidirectional"))
      (node (ref "R24") (pin "1") (pinfunction "1_1") (pintype "passive"))
      (node (ref "R6") (pin "1") (pinfunction "1_1") (pintype "passive"))
    )
    (net (code "62") (name "Net-(DD1-BOOT0)") (class "Default")
      (node (ref "DD1") (pin "94") (pinfunction "BOOT0_94") (pintype "bidirectional"))
      (node (ref "JP2") (pin "1") (pinfunction "1_1") (pintype "passive"))
      (node (ref "R8") (pin "1") (pinfunction "1_1") (pintype "passive"))
    )
    (net (code "63") (name "Net-(DD1-NC)") (class "Default")
      (node (ref "C26") (pin "1") (pinfunction "1_1") (pintype "passive"))
      (node (ref "DD1") (pin "73") (pinfunction "NC_73") (pintype "bidirectional"))
    )
    (net (code "64") (name "Net-(DD1-NRST)") (class "Default")
      (node (ref "C25") (pin "1") (pinfunction "1_1") (pintype "passive"))
      (node (ref "DD1") (pin "14") (pinfunction "NRST_14") (pintype "bidirectional"))
      (node (ref "R9") (pin "2") (pinfunction "2_2") (pintype "passive"))
    )
    (net (code "65") (name "Net-(DD1-OSCIN)") (class "Default")
      (node (ref "DD1") (pin "12") (pinfunction "OSCIN_12") (pintype "bidirectional"))
      (node (ref "R15") (pin "1") (pinfunction "1_1") (pintype "passive"))
    )
    (net (code "66") (name "Net-(DD1-OSCOUT)") (class "Default")
      (node (ref "DD1") (pin "13") (pinfunction "OSCOUT_13") (pintype "bidirectional"))
      (node (ref "ZQ1") (pin "1") (pinfunction "1_1") (pintype "bidirectional"))
    )
    (net (code "67") (name "Net-(DD1-PA11)") (class "Default")
      (node (ref "DD1") (pin "70") (pinfunction "PA11_70") (pintype "bidirectional"))
      (node (ref "R1") (pin "1") (pinfunction "1_1") (pintype "passive"))
    )
    (net (code "68") (name "Net-(DD1-PA12)") (class "Default")
      (node (ref "DD1") (pin "71") (pinfunction "PA12_71") (pintype "bidirectional"))
      (node (ref "R2") (pin "1") (pinfunction "1_1") (pintype "passive"))
      (node (ref "R3") (pin "2") (pinfunction "2_2") (pintype "passive"))
    )
    (net (code "69") (name "Net-(DD1-PD4)") (class "Default")
      (node (ref "DD1") (pin "85") (pinfunction "PD4_85") (pintype "bidirectional"))
      (node (ref "R4") (pin "2") (pinfunction "2_2") (pintype "passive"))
      (node (ref "R5") (pin "2") (pinfunction "2_2") (pintype "passive"))
    )
    (net (code "70") (name "Net-(DD1-PD11)") (class "Default")
      (node (ref "DD1") (pin "58") (pinfunction "PD11_58") (pintype "bidirectional"))
      (node (ref "R23") (pin "2") (pinfunction "2_2") (pintype "passive"))
    )
    (net (code "71") (name "Net-(DD1-PE0)") (class "Default")
      (node (ref "DD1") (pin "97") (pinfunction "PE0_97") (pintype "bidirectional"))
      (node (ref "RN3") (pin "5") (pinfunction "2_5") (pintype "passive"))
    )
    (net (code "72") (name "Net-(DD1-PE1)") (class "Default")
      (node (ref "DD1") (pin "98") (pinfunction "PE1_98") (pintype "bidirectional"))
      (node (ref "RN3") (pin "6") (pinfunction "2_6") (pintype "passive"))
    )
    (net (code "73") (name "Net-(DD1-PE2)") (class "Default")
      (node (ref "DD1") (pin "1") (pinfunction "PE2_1") (pintype "bidirectional"))
      (node (ref "RN3") (pin "7") (pinfunction "2_7") (pintype "passive"))
    )
    (net (code "74") (name "Net-(DD1-PE3)") (class "Default")
      (node (ref "DD1") (pin "2") (pinfunction "PE3_2") (pintype "bidirectional"))
      (node (ref "RN3") (pin "8") (pinfunction "2_8") (pintype "passive"))
    )
    (net (code "75") (name "Net-(DD1-VSS2)") (class "Default")
      (node (ref "C4") (pin "1") (pinfunction "1_1") (pintype "passive"))
      (node (ref "DD1") (pin "49") (pinfunction "VSS2_49") (pintype "bidirectional"))
    )
    (net (code "76") (name "Net-(DD2-C1)") (class "Default")
      (node (ref "C10") (pin "1") (pinfunction "1_1") (pintype "passive"))
      (node (ref "DD2") (pin "10") (pinfunction "C1_10") (pintype "bidirectional"))
    )
    (net (code "77") (name "Net-(DD2-STEP_C)") (class "Default")
      (node (ref "C11") (pin "2") (pinfunction "2_2") (pintype "passive"))
      (node (ref "DD2") (pin "12") (pinfunction "STEP_C_12") (pintype "bidirectional"))
    )
    (net (code "78") (name "Net-(DD2-STEP_P)") (class "Default")
      (node (ref "C11") (pin "1") (pinfunction "1_1") (pintype "passive"))
      (node (ref "DD2") (pin "8") (pinfunction "STEP_P_8") (pintype "bidirectional"))
    )
    (net (code "79") (name "Net-(DD4-CPUOT)") (class "Default")
      (node (ref "C16") (pin "1") (pinfunction "1_1") (pintype "passive"))
      (node (ref "DD4") (pin "20") (pinfunction "CPUOT_20") (pintype "bidirectional"))
    )
    (net (code "80") (name "Net-(DD4-REGOUT)") (class "Default")
      (node (ref "C17") (pin "1") (pinfunction "1_1") (pintype "passive"))
      (node (ref "DD4") (pin "10") (pinfunction "REGOUT_10") (pintype "bidirectional"))
    )
    (net (code "81") (name "Net-(LED1-PadA)") (class "Default")
      (node (ref "LED1") (pin "A") (pinfunction "A_A") (pintype "passive"))
      (node (ref "R20") (pin "2") (pinfunction "2_2") (pintype "passive"))
    )
    (net (code "82") (name "Net-(LED3-PadA)") (class "Default")
      (node (ref "LED3") (pin "A") (pinfunction "A_A") (pintype "passive"))
      (node (ref "R6") (pin "2") (pinfunction "2_2") (pintype "passive"))
    )
    (net (code "83") (name "Net-(LED6-PadA)") (class "Default")
      (node (ref "LED6") (pin "A") (pinfunction "A_A") (pintype "passive"))
      (node (ref "RN3") (pin "1") (pinfunction "1_1") (pintype "passive"))
    )
    (net (code "84") (name "Net-(R1-Pad2)") (class "Default")
      (node (ref "R1") (pin "2") (pinfunction "2_2") (pintype "passive"))
      (node (ref "USB") (pin "2") (pinfunction "2_2") (pintype "passive"))
    )
    (net (code "85") (name "Net-(R2-Pad2)") (class "Default")
      (node (ref "R2") (pin "2") (pinfunction "2_2") (pintype "passive"))
      (node (ref "USB") (pin "3") (pinfunction "3_3") (pintype "passive"))
    )
    (net (code "86") (name "Net-(R15-Pad2)") (class "Default")
      (node (ref "R15") (pin "2") (pinfunction "2_2") (pintype "passive"))
      (node (ref "ZQ1") (pin "3") (pinfunction "3_3") (pintype "bidirectional"))
    )
    (net (code "87") (name "Net-(RADIO_IN-Pad2)") (class "Default")
      (node (ref "RADIO_IN") (pin "2") (pinfunction "2_2") (pintype "passive"))
      (node (ref "RN2") (pin "1") (pinfunction "1_1") (pintype "passive"))
    )
    (net (code "88") (name "Net-(RADIO_IN-Pad5)") (class "Default")
      (node (ref "RADIO_IN") (pin "5") (pinfunction "5_5") (pintype "passive"))
      (node (ref "RN1") (pin "1") (pinfunction "1_1") (pintype "passive"))
    )
    (net (code "89") (name "Net-(RN1B-1)") (class "Default")
      (node (ref "RADIO_IN") (pin "6") (pinfunction "6_6") (pintype "passive"))
      (node (ref "RN1") (pin "2") (pinfunction "1_2") (pintype "passive"))
    )
    (net (code "90") (name "Net-(RN1C-1)") (class "Default")
      (node (ref "RADIO_IN") (pin "7") (pinfunction "7_7") (pintype "passive"))
      (node (ref "RN1") (pin "3") (pinfunction "1_3") (pintype "passive"))
    )
    (net (code "91") (name "Net-(RN1D-1)") (class "Default")
      (node (ref "RADIO_IN") (pin "9") (pinfunction "9_9") (pintype "passive"))
      (node (ref "RN1") (pin "4") (pinfunction "1_4") (pintype "passive"))
    )
    (net (code "92") (name "Net-(RN2B-1)") (class "Default")
      (node (ref "RADIO_IN") (pin "1") (pinfunction "1_1") (pintype "passive"))
      (node (ref "RN2") (pin "2") (pinfunction "1_2") (pintype "passive"))
    )
    (net (code "93") (name "Net-(RN2C-1)") (class "Default")
      (node (ref "RADIO_IN") (pin "4") (pinfunction "4_4") (pintype "passive"))
      (node (ref "RN2") (pin "3") (pinfunction "1_3") (pintype "passive"))
    )
    (net (code "94") (name "Net-(RN2D-1)") (class "Default")
      (node (ref "RADIO_IN") (pin "3") (pinfunction "3_3") (pintype "passive"))
      (node (ref "RN2") (pin "4") (pinfunction "1_4") (pintype "passive"))
    )
    (net (code "95") (name "Net-(RN3B-1)") (class "Default")
      (node (ref "LED5") (pin "A") (pinfunction "A_A") (pintype "passive"))
      (node (ref "RN3") (pin "2") (pinfunction "1_2") (pintype "passive"))
    )
    (net (code "96") (name "Net-(RN3C-1)") (class "Default")
      (node (ref "LED4") (pin "A") (pinfunction "A_A") (pintype "passive"))
      (node (ref "RN3") (pin "3") (pinfunction "1_3") (pintype "passive"))
    )
    (net (code "97") (name "Net-(RN3D-1)") (class "Default")
      (node (ref "LED2") (pin "A") (pinfunction "A_A") (pintype "passive"))
      (node (ref "RN3") (pin "4") (pinfunction "1_4") (pintype "passive"))
    )
    (net (code "98") (name "V+") (class "Default")
      (node (ref "C14") (pin "1") (pinfunction "1_1") (pintype "passive"))
      (node (ref "C15") (pin "1") (pinfunction "1_1") (pintype "passive"))
      (node (ref "DD1") (pin "21") (pinfunction "VREF+_21") (pintype "bidirectional"))
      (node (ref "DD1") (pin "22") (pinfunction "VDDA_22") (pintype "bidirectional"))
      (node (ref "DD2") (pin "2") (pinfunction "VDD_2") (pintype "bidirectional"))
      (node (ref "DD2") (pin "4") (pinfunction "S1_4") (pintype "bidirectional"))
      (node (ref "DD4") (pin "13") (pinfunction "VDD_13") (pintype "bidirectional"))
      (node (ref "R24") (pin "2") (pinfunction "2_2") (pintype "passive"))
    )
    (net (code "99") (name "VCC") (class "Default")
      (node (ref "C13") (pin "+") (pinfunction "+_+") (pintype "passive"))
      (node (ref "C18") (pin "1") (pinfunction "1_1") (pintype "passive"))
      (node (ref "C19") (pin "1") (pinfunction "1_1") (pintype "passive"))
      (node (ref "C8") (pin "1") (pinfunction "1_1") (pintype "passive"))
      (node (ref "C9") (pin "1") (pinfunction "1_1") (pintype "passive"))
      (node (ref "DA1") (pin "5") (pinfunction "OUT_5") (pintype "bidirectional"))
      (node (ref "DD1") (pin "100") (pinfunction "VDD3_100") (pintype "bidirectional"))
      (node (ref "DD1") (pin "11") (pinfunction "VDD5_11") (pintype "bidirectional"))
      (node (ref "DD1") (pin "19") (pinfunction "VSSA_19") (pintype "bidirectional"))
      (node (ref "DD1") (pin "28") (pinfunction "VDD4_28") (pintype "bidirectional"))
      (node (ref "DD1") (pin "50") (pinfunction "VDD1_50") (pintype "bidirectional"))
      (node (ref "DD1") (pin "6") (pinfunction "VBAT_6") (pintype "bidirectional"))
      (node (ref "DD1") (pin "75") (pinfunction "VDD2_75") (pintype "bidirectional"))
      (node (ref "DD2") (pin "13") (pinfunction "VDD_IO_13") (pintype "bidirectional"))
      (node (ref "DD3") (pin "7") (pinfunction "VCC_7") (pintype "bidirectional"))
      (node (ref "DD3") (pin "8") (pinfunction "WC_8") (pintype "bidirectional"))
      (node (ref "DD5") (pin "1") (pinfunction "VDD_1") (pintype "bidirectional"))
      (node (ref "DD5") (pin "4") (pinfunction "CS1_4") (pintype "bidirectional"))
      (node (ref "DD5") (pin "5") (pinfunction "CS_5") (pintype "bidirectional"))
      (node (ref "DD6") (pin "3") (pinfunction "WP_3") (pintype "bidirectional"))
      (node (ref "DD6") (pin "7") (pinfunction "HOLD_7") (pintype "bidirectional"))
      (node (ref "DD6") (pin "8") (pinfunction "VCC_8") (pintype "bidirectional"))
      (node (ref "JP2") (pin "2") (pinfunction "2_2") (pintype "passive"))
      (node (ref "R10") (pin "1") (pinfunction "1_1") (pintype "passive"))
      (node (ref "R12") (pin "1") (pinfunction "1_1") (pintype "passive"))
      (node (ref "R14") (pin "2") (pinfunction "2_2") (pintype "passive"))
      (node (ref "R20") (pin "1") (pinfunction "1_1") (pintype "passive"))
      (node (ref "R3") (pin "1") (pinfunction "1_1") (pintype "passive"))
      (node (ref "R7") (pin "2") (pinfunction "2_2") (pintype "passive"))
      (node (ref "R9") (pin "1") (pinfunction "1_1") (pintype "passive"))
    )
    (net (code "100") (name "unconnected-(DD1-PA8-Pad67)") (class "Default")
      (node (ref "DD1") (pin "67") (pinfunction "PA8_67") (pintype "bidirectional"))
    )
    (net (code "101") (name "unconnected-(DD1-PA13-Pad72)") (class "Default")
      (node (ref "DD1") (pin "72") (pinfunction "PA13_72") (pintype "bidirectional"))
    )
    (net (code "102") (name "unconnected-(DD1-PA14-Pad76)") (class "Default")
      (node (ref "DD1") (pin "76") (pinfunction "PA14_76") (pintype "bidirectional"))
    )
    (net (code "103") (name "unconnected-(DD1-PC5-Pad34)") (class "Default")
      (node (ref "DD1") (pin "34") (pinfunction "PC5_34") (pintype "bidirectional"))
    )
    (net (code "104") (name "unconnected-(DD1-PC10-Pad78)") (class "Default")
      (node (ref "DD1") (pin "78") (pinfunction "PC10_78") (pintype "bidirectional"))
    )
    (net (code "105") (name "unconnected-(DD1-PC11-Pad79)") (class "Default")
      (node (ref "DD1") (pin "79") (pinfunction "PC11_79") (pintype "bidirectional"))
    )
    (net (code "106") (name "unconnected-(DD1-PC12-Pad80)") (class "Default")
      (node (ref "DD1") (pin "80") (pinfunction "PC12_80") (pintype "bidirectional"))
    )
    (net (code "107") (name "unconnected-(DD1-PC13-Pad7)") (class "Default")
      (node (ref "DD1") (pin "7") (pinfunction "PC13_7") (pintype "bidirectional"))
    )
    (net (code "108") (name "unconnected-(DD1-PD0-Pad81)") (class "Default")
      (node (ref "DD1") (pin "81") (pinfunction "PD0_81") (pintype "bidirectional"))
    )
    (net (code "109") (name "unconnected-(DD1-PD1-Pad82)") (class "Default")
      (node (ref "DD1") (pin "82") (pinfunction "PD1_82") (pintype "bidirectional"))
    )
    (net (code "110") (name "unconnected-(DD1-PD2-Pad83)") (class "Default")
      (node (ref "DD1") (pin "83") (pinfunction "PD2_83") (pintype "bidirectional"))
    )
    (net (code "111") (name "unconnected-(DD1-PD3-Pad84)") (class "Default")
      (node (ref "DD1") (pin "84") (pinfunction "PD3_84") (pintype "bidirectional"))
    )
    (net (code "112") (name "unconnected-(DD1-PD7-Pad88)") (class "Default")
      (node (ref "DD1") (pin "88") (pinfunction "PD7_88") (pintype "bidirectional"))
    )
    (net (code "113") (name "unconnected-(DD1-PD12-Pad59)") (class "Default")
      (node (ref "DD1") (pin "59") (pinfunction "PD12_59") (pintype "bidirectional"))
    )
    (net (code "114") (name "unconnected-(DD1-PE4-Pad3)") (class "Default")
      (node (ref "DD1") (pin "3") (pinfunction "PE4_3") (pintype "bidirectional"))
    )
    (net (code "115") (name "unconnected-(DD1-PE7-Pad38)") (class "Default")
      (node (ref "DD1") (pin "38") (pinfunction "PE7_38") (pintype "bidirectional"))
    )
    (net (code "116") (name "unconnected-(DD1-PE8-Pad39)") (class "Default")
      (node (ref "DD1") (pin "39") (pinfunction "PE8_39") (pintype "bidirectional"))
    )
    (net (code "117") (name "unconnected-(DD1-PE10-Pad41)") (class "Default")
      (node (ref "DD1") (pin "41") (pinfunction "PE10_41") (pintype "bidirectional"))
    )
    (net (code "118") (name "unconnected-(DD1-PE12-Pad43)") (class "Default")
      (node (ref "DD1") (pin "43") (pinfunction "PE12_43") (pintype "bidirectional"))
    )
    (net (code "119") (name "unconnected-(DD1-PE15-Pad46)") (class "Default")
      (node (ref "DD1") (pin "46") (pinfunction "PE15_46") (pintype "bidirectional"))
    )
    (net (code "120") (name "unconnected-(DD2-NC1-Pad3)") (class "Default")
      (node (ref "DD2") (pin "3") (pinfunction "NC1_3") (pintype "bidirectional"))
    )
    (net (code "121") (name "unconnected-(DD2-NC2-Pad5)") (class "Default")
      (node (ref "DD2") (pin "5") (pinfunction "NC2_5") (pintype "bidirectional"))
    )
    (net (code "122") (name "unconnected-(DD2-NC3-Pad6)") (class "Default")
      (node (ref "DD2") (pin "6") (pinfunction "NC3_6") (pintype "bidirectional"))
    )
    (net (code "123") (name "unconnected-(DD2-NC4-Pad7)") (class "Default")
      (node (ref "DD2") (pin "7") (pinfunction "NC4_7") (pintype "bidirectional"))
    )
    (net (code "124") (name "unconnected-(DD2-NC5-Pad14)") (class "Default")
      (node (ref "DD2") (pin "14") (pinfunction "NC5_14") (pintype "bidirectional"))
    )
    (net (code "125") (name "unconnected-(DD4-AUXCL-Pad7)") (class "Default")
      (node (ref "DD4") (pin "7") (pinfunction "AUXCL_7") (pintype "bidirectional"))
    )
    (net (code "126") (name "unconnected-(DD4-AUXDA-Pad6)") (class "Default")
      (node (ref "DD4") (pin "6") (pinfunction "AUXDA_6") (pintype "bidirectional"))
    )
    (net (code "127") (name "unconnected-(DD4-CLKOUT-Pad22)") (class "Default")
      (node (ref "DD4") (pin "22") (pinfunction "CLKOUT_22") (pintype "bidirectional"))
    )
    (net (code "128") (name "unconnected-(DD4-NC1-Pad2)") (class "Default")
      (node (ref "DD4") (pin "2") (pinfunction "NC1_2") (pintype "bidirectional"))
    )
    (net (code "129") (name "unconnected-(DD4-NC3-Pad4)") (class "Default")
      (node (ref "DD4") (pin "4") (pinfunction "NC3_4") (pintype "bidirectional"))
    )
    (net (code "130") (name "unconnected-(DD4-NC4-Pad5)") (class "Default")
      (node (ref "DD4") (pin "5") (pinfunction "NC4_5") (pintype "bidirectional"))
    )
    (net (code "131") (name "unconnected-(DD4-NC5-Pad14)") (class "Default")
      (node (ref "DD4") (pin "14") (pinfunction "NC5_14") (pintype "bidirectional"))
    )
    (net (code "132") (name "unconnected-(DD4-NC6-Pad15)") (class "Default")
      (node (ref "DD4") (pin "15") (pinfunction "NC6_15") (pintype "bidirectional"))
    )
    (net (code "133") (name "unconnected-(DD4-NC7-Pad16)") (class "Default")
      (node (ref "DD4") (pin "16") (pinfunction "NC7_16") (pintype "bidirectional"))
    )
    (net (code "134") (name "unconnected-(DD4-NC8-Pad17)") (class "Default")
      (node (ref "DD4") (pin "17") (pinfunction "NC8_17") (pintype "bidirectional"))
    )
    (net (code "135") (name "unconnected-(DD4-NS2-Pad3)") (class "Default")
      (node (ref "DD4") (pin "3") (pinfunction "NS2_3") (pintype "bidirectional"))
    )
    (net (code "136") (name "unconnected-(DD4-RESV1-Pad21)") (class "Default")
      (node (ref "DD4") (pin "21") (pinfunction "RESV1_21") (pintype "bidirectional"))
    )
    (net (code "137") (name "unconnected-(DD4-RESV2-Pad19)") (class "Default")
      (node (ref "DD4") (pin "19") (pinfunction "RESV2_19") (pintype "bidirectional"))
    )
    (net (code "138") (name "unconnected-(DD5-MISO-Pad6)") (class "Default")
      (node (ref "DD5") (pin "6") (pinfunction "MISO_6") (pintype "bidirectional"))
    )
    (net (code "139") (name "unconnected-(USB-Pad4)") (class "Default")
      (node (ref "USB") (pin "4") (pinfunction "4_4") (pintype "passive"))
    )
  )
)
